# piezo-preamp-tickler_V1-01a_two_buffers.net
KiCad netlist of a schematic drawn in EAGLE
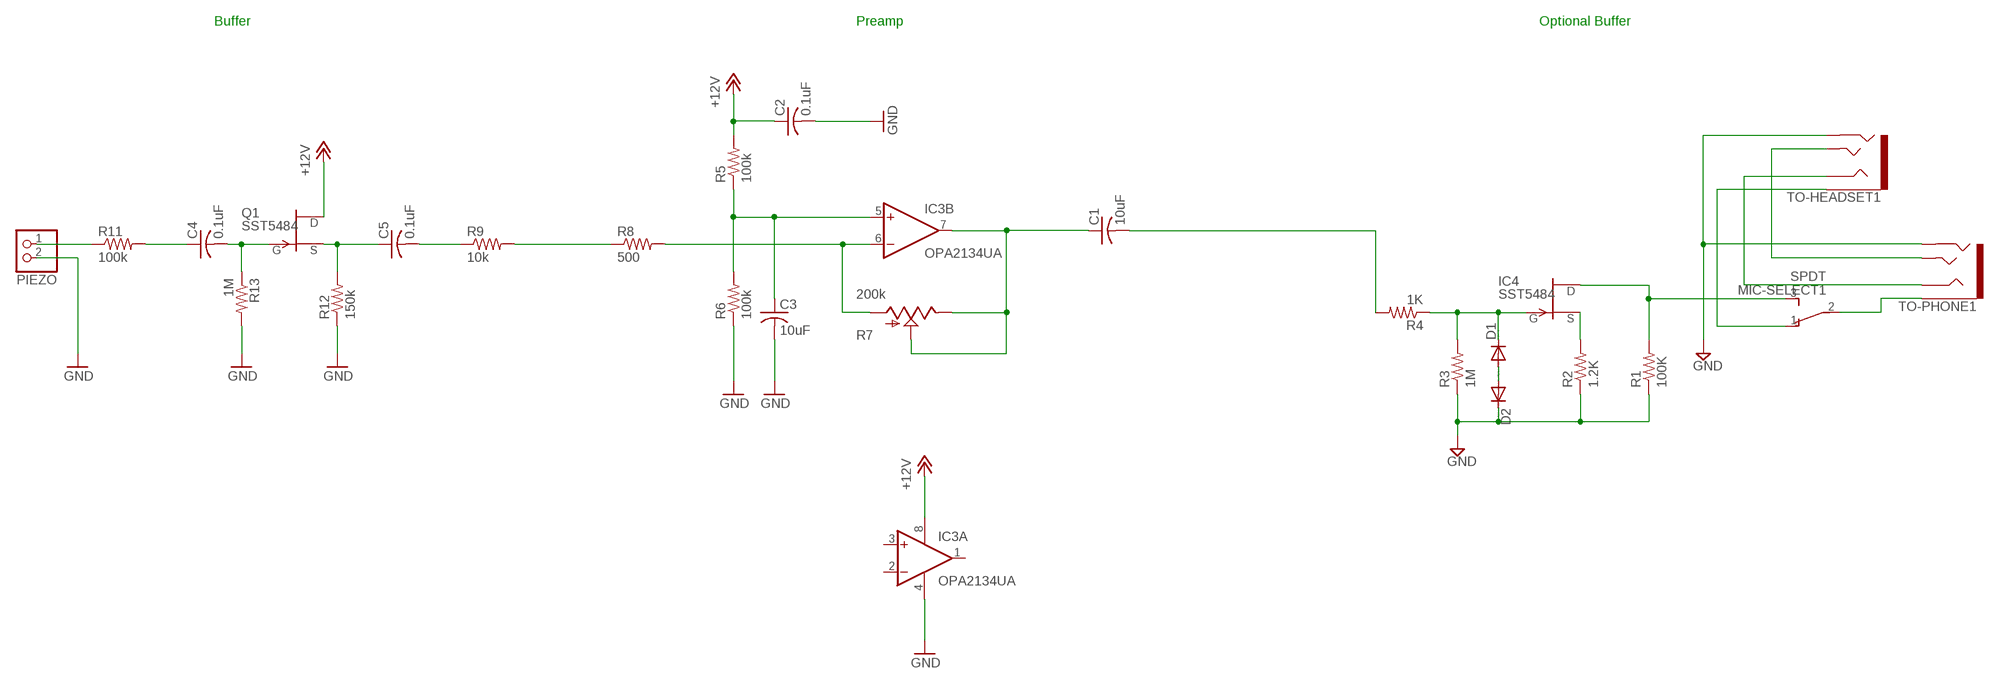
[diagram p0: schematic, sheet 1]
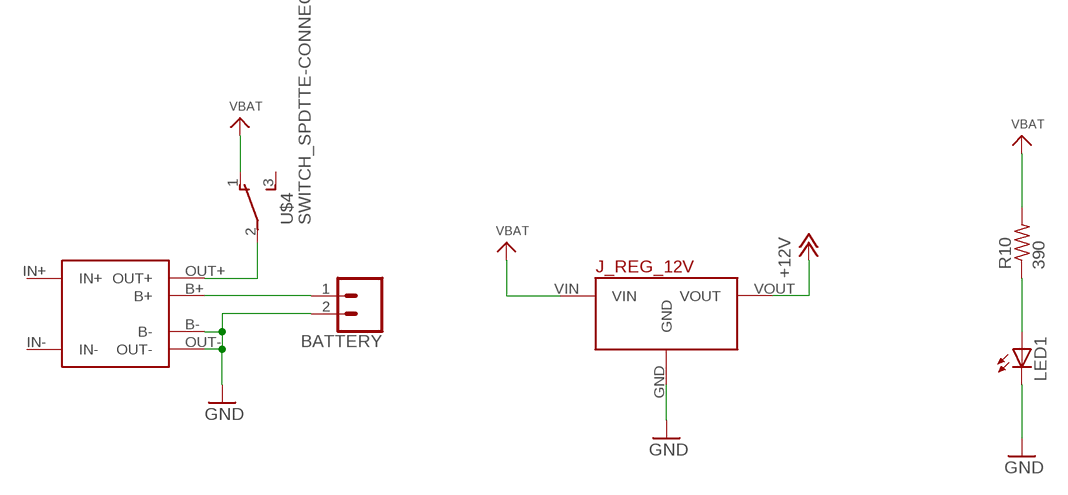
[diagram p1: schematic, sheet 2]

(export (version "E")
  (design (tool "Eeschema 10.0.6"))
  (components
    (comp (ref "BATTERY")
      (value "CONN_02LOCK")
      (footprint "eagle-import:1X02_LOCK")
      (libsource (lib "eagle-import") (part "CONN_02LOCK"))
    )
    (comp (ref "J_REG_12V")
      (value "POLOLU_VOLTAGE_REGULATORS_3PIN")
      (footprint "eagle-import:POLOLU_5V-12V_STEPUP_U3V12F5-U3V12F12")
      (libsource (lib "eagle-import") (part "POLOLU_VOLTAGE_REGULATORS_3PIN"))
    )
    (comp (ref "LED1")
      (value "LED3MM")
      (footprint "eagle-import:LED3MM")
      (libsource (lib "eagle-import") (part "LED3MM"))
    )
    (comp (ref "R10")
      (value "390")
      (footprint "eagle-import:R0805")
      (libsource (lib "eagle-import") (part "adafruit_R-US_R0805"))
    )
    (comp (ref "U$4")
      (value "SWITCH_SPDTTE-CONNECT")
      (footprint "eagle-import:SWITCH_SPDT-TE-CONNECT")
      (libsource (lib "eagle-import") (part "SWITCH_SPDTTE-CONNECT"))
    )
    (comp (ref "U$6")
      (value "TP4056-MODULE")
      (footprint "eagle-import:TP4056-LITHIUM-PROTECTED-MODULE")
      (libsource (lib "eagle-import") (part "TP4056-MODULE"))
    )
    (comp (ref "C1")
      (value "10uF")
      (footprint "eagle-import:C0805")
      (libsource (lib "eagle-import") (part "C-USC0805"))
    )
    (comp (ref "C2")
      (value "0.1uF")
      (footprint "eagle-import:C0805")
      (libsource (lib "eagle-import") (part "C-USC0805"))
    )
    (comp (ref "C3")
      (value "10uF")
      (footprint "eagle-import:C0805")
      (libsource (lib "eagle-import") (part "C-USC0805"))
    )
    (comp (ref "C4")
      (value "0.1uF")
      (footprint "eagle-import:C0805")
      (libsource (lib "eagle-import") (part "C-USC0805"))
    )
    (comp (ref "C5")
      (value "0.1uF")
      (footprint "eagle-import:C0805")
      (libsource (lib "eagle-import") (part "C-USC0805"))
    )
    (comp (ref "D1")
      (value "DIODE-SOD123")
      (footprint "eagle-import:SOD123")
      (libsource (lib "eagle-import") (part "DIODE-SOD123"))
    )
    (comp (ref "D2")
      (value "DIODE-SOD123")
      (footprint "eagle-import:SOD123")
      (libsource (lib "eagle-import") (part "DIODE-SOD123"))
    )
    (comp (ref "IC3")
      (value "OPA2134UA")
      (footprint "eagle-import:SO08")
      (libsource (lib "eagle-import") (part "OPA2UA134"))
    )
    (comp (ref "IC4")
      (value "SST5484")
      (footprint "eagle-import:SOT23")
      (libsource (lib "eagle-import") (part "?548SST4"))
    )
    (comp (ref "MIC-SELECT1")
      (value "SPDT")
      (footprint "eagle-import:SWITCH_SPDT-TE-CONNECT")
      (libsource (lib "eagle-import") (part "SWITCH_SPDTTE-CONNECT"))
    )
    (comp (ref "PIEZO")
      (value "JST_2PIN-THM")
      (footprint "eagle-import:JST-PH-2-THM")
      (libsource (lib "eagle-import") (part "JST_2PIN-THM"))
    )
    (comp (ref "Q1")
      (value "SST5484")
      (footprint "eagle-import:SOT23")
      (libsource (lib "eagle-import") (part "?548SST4"))
    )
    (comp (ref "R1")
      (value "100K")
      (footprint "eagle-import:R0603")
      (libsource (lib "eagle-import") (part "R-US_R0603"))
    )
    (comp (ref "R2")
      (value "1.2K")
      (footprint "eagle-import:R0603")
      (libsource (lib "eagle-import") (part "R-US_R0603"))
    )
    (comp (ref "R3")
      (value "1M")
      (footprint "eagle-import:R0603")
      (libsource (lib "eagle-import") (part "R-US_R0603"))
    )
    (comp (ref "R4")
      (value "1K")
      (footprint "eagle-import:R0603")
      (libsource (lib "eagle-import") (part "R-US_R0603"))
    )
    (comp (ref "R5")
      (value "100k")
      (footprint "eagle-import:R0603")
      (libsource (lib "eagle-import") (part "resistor_R-US_R0603"))
    )
    (comp (ref "R6")
      (value "100k")
      (footprint "eagle-import:R0603")
      (libsource (lib "eagle-import") (part "resistor_R-US_R0603"))
    )
    (comp (ref "R7")
      (value "200k")
      (footprint "eagle-import:TRIMPOT-BOURNS-3306W")
      (libsource (lib "eagle-import") (part "TRIMPOT-BOURNS3306W"))
    )
    (comp (ref "R8")
      (value "500")
      (footprint "eagle-import:R0603")
      (libsource (lib "eagle-import") (part "resistor_R-US_R0603"))
    )
    (comp (ref "R9")
      (value "10k")
      (footprint "eagle-import:R0603")
      (libsource (lib "eagle-import") (part "resistor_R-US_R0603"))
    )
    (comp (ref "R11")
      (value "100k")
      (footprint "eagle-import:R0603")
      (libsource (lib "eagle-import") (part "resistor_R-US_R0603"))
    )
    (comp (ref "R12")
      (value "150k")
      (footprint "eagle-import:R0603")
      (libsource (lib "eagle-import") (part "resistor_R-US_R0603"))
    )
    (comp (ref "R13")
      (value "1M")
      (footprint "eagle-import:R0603")
      (libsource (lib "eagle-import") (part "resistor_R-US_R0603"))
    )
    (comp (ref "TO-HEADSET1")
      (value "AUDIO-JACK3LGPADS")
      (footprint "eagle-import:AUDIO-JACK-TRRS-SMD")
      (libsource (lib "eagle-import") (part "AUDIO-JACK3LGPADS"))
    )
    (comp (ref "TO-PHONE1")
      (value "AUDIO-JACK3LGPADS")
      (footprint "eagle-import:AUDIO-JACK-TRRS-SMD")
      (libsource (lib "eagle-import") (part "AUDIO-JACK3LGPADS"))
    )
  )
  (nets
    (net (code "1") (name "+12V") (class "Default")
      (node (ref "C2") (pin "1") (pinfunction "1_1") (pintype "passive"))
      (node (ref "IC3") (pin "8") (pinfunction "V+_8") (pintype "power_in"))
      (node (ref "J_REG_12V") (pin "VOUT") (pinfunction "VOUT_VOUT") (pintype "bidirectional"))
      (node (ref "Q1") (pin "1") (pinfunction "D_1") (pintype "passive"))
      (node (ref "R5") (pin "2") (pinfunction "2_2") (pintype "passive"))
    )
    (net (code "2") (name "GND") (class "Default")
      (node (ref "BATTERY") (pin "2") (pinfunction "2_2") (pintype "passive"))
      (node (ref "C2") (pin "2") (pinfunction "2_2") (pintype "passive"))
      (node (ref "C3") (pin "2") (pinfunction "2_2") (pintype "passive"))
      (node (ref "D2") (pin "C") (pinfunction "C_C") (pintype "passive"))
      (node (ref "IC3") (pin "4") (pinfunction "V-_4") (pintype "power_in"))
      (node (ref "J_REG_12V") (pin "GND") (pinfunction "GND_GND") (pintype "bidirectional"))
      (node (ref "LED1") (pin "K") (pinfunction "C_K") (pintype "passive"))
      (node (ref "PIEZO") (pin "2") (pinfunction "1_2") (pintype "passive"))
      (node (ref "R1") (pin "1") (pinfunction "1_1") (pintype "passive"))
      (node (ref "R12") (pin "1") (pinfunction "1_1") (pintype "passive"))
      (node (ref "R13") (pin "2") (pinfunction "2_2") (pintype "passive"))
      (node (ref "R2") (pin "1") (pinfunction "1_1") (pintype "passive"))
      (node (ref "R3") (pin "1") (pinfunction "1_1") (pintype "passive"))
      (node (ref "R6") (pin "1") (pinfunction "1_1") (pintype "passive"))
      (node (ref "TO-HEADSET1") (pin "RING2") (pinfunction "RING2_RING2") (pintype "bidirectional"))
      (node (ref "TO-PHONE1") (pin "RING2") (pinfunction "RING2_RING2") (pintype "bidirectional"))
      (node (ref "U$6") (pin "B-") (pinfunction "B-_B-") (pintype "power_in"))
      (node (ref "U$6") (pin "OUT-") (pinfunction "OUT-_OUT-") (pintype "power_in"))
    )
    (net (code "3") (name "IN+") (class "Default")
      (node (ref "U$6") (pin "IN+") (pinfunction "IN+_IN+") (pintype "power_in"))
    )
    (net (code "4") (name "IN-") (class "Default")
      (node (ref "U$6") (pin "IN-") (pinfunction "IN-_IN-") (pintype "power_in"))
    )
    (net (code "5") (name "Net-(BATTERY-Pad1)") (class "Default")
      (node (ref "BATTERY") (pin "1") (pinfunction "1_1") (pintype "passive"))
      (node (ref "U$6") (pin "B+") (pinfunction "B+_B+") (pintype "power_in"))
    )
    (net (code "6") (name "Net-(C1-Pad2)") (class "Default")
      (node (ref "C1") (pin "2") (pinfunction "2_2") (pintype "passive"))
      (node (ref "R4") (pin "2") (pinfunction "2_2") (pintype "passive"))
    )
    (net (code "7") (name "Net-(C4-Pad1)") (class "Default")
      (node (ref "C4") (pin "1") (pinfunction "1_1") (pintype "passive"))
      (node (ref "R11") (pin "2") (pinfunction "2_2") (pintype "passive"))
    )
    (net (code "8") (name "Net-(C5-Pad2)") (class "Default")
      (node (ref "C5") (pin "2") (pinfunction "2_2") (pintype "passive"))
      (node (ref "R9") (pin "1") (pinfunction "1_1") (pintype "passive"))
    )
    (net (code "9") (name "Net-(D1-PadA)") (class "Default")
      (node (ref "D1") (pin "A") (pinfunction "A_A") (pintype "passive"))
      (node (ref "D2") (pin "A") (pinfunction "A_A") (pintype "passive"))
    )
    (net (code "10") (name "Net-(IC3B-+IN)") (class "Default")
      (node (ref "C3") (pin "1") (pinfunction "1_1") (pintype "passive"))
      (node (ref "IC3") (pin "5") (pinfunction "+IN_5") (pintype "input"))
      (node (ref "R5") (pin "1") (pinfunction "1_1") (pintype "passive"))
      (node (ref "R6") (pin "2") (pinfunction "2_2") (pintype "passive"))
    )
    (net (code "11") (name "Net-(IC3B--IN)") (class "Default")
      (node (ref "IC3") (pin "6") (pinfunction "-IN_6") (pintype "input"))
      (node (ref "R7") (pin "P$1") (pinfunction "IN_P$1") (pintype "passive"))
      (node (ref "R8") (pin "2") (pinfunction "2_2") (pintype "passive"))
    )
    (net (code "12") (name "Net-(IC3B-OUT)") (class "Default")
      (node (ref "C1") (pin "1") (pinfunction "1_1") (pintype "passive"))
      (node (ref "IC3") (pin "7") (pinfunction "OUT_7") (pintype "output"))
      (node (ref "R7") (pin "P$2") (pinfunction "WIPER_P$2") (pintype "passive"))
      (node (ref "R7") (pin "P$3") (pinfunction "OUT_P$3") (pintype "passive"))
    )
    (net (code "13") (name "Net-(IC4-D)") (class "Default")
      (node (ref "IC4") (pin "1") (pinfunction "D_1") (pintype "passive"))
      (node (ref "MIC-SELECT1") (pin "3") (pinfunction "3_3") (pintype "passive"))
      (node (ref "R1") (pin "2") (pinfunction "2_2") (pintype "passive"))
    )
    (net (code "14") (name "Net-(IC4-G)") (class "Default")
      (node (ref "D1") (pin "C") (pinfunction "C_C") (pintype "passive"))
      (node (ref "IC4") (pin "3") (pinfunction "G_3") (pintype "passive"))
      (node (ref "R3") (pin "2") (pinfunction "2_2") (pintype "passive"))
      (node (ref "R4") (pin "1") (pinfunction "1_1") (pintype "passive"))
    )
    (net (code "15") (name "Net-(IC4-S)") (class "Default")
      (node (ref "IC4") (pin "2") (pinfunction "S_2") (pintype "passive"))
      (node (ref "R2") (pin "2") (pinfunction "2_2") (pintype "passive"))
    )
    (net (code "16") (name "Net-(LED1-PadA)") (class "Default")
      (node (ref "LED1") (pin "A") (pinfunction "A_A") (pintype "passive"))
      (node (ref "R10") (pin "1") (pinfunction "1_1") (pintype "passive"))
    )
    (net (code "17") (name "Net-(MIC-SELECT1-Pad1)") (class "Default")
      (node (ref "MIC-SELECT1") (pin "1") (pinfunction "1_1") (pintype "passive"))
      (node (ref "TO-HEADSET1") (pin "EARTH") (pinfunction "EARTH_EARTH") (pintype "bidirectional"))
    )
    (net (code "18") (name "Net-(MIC-SELECT1-Pad2)") (class "Default")
      (node (ref "MIC-SELECT1") (pin "2") (pinfunction "2_2") (pintype "passive"))
      (node (ref "TO-PHONE1") (pin "EARTH") (pinfunction "EARTH_EARTH") (pintype "bidirectional"))
    )
    (net (code "19") (name "Net-(PIEZO-2)") (class "Default")
      (node (ref "PIEZO") (pin "1") (pinfunction "2_1") (pintype "passive"))
      (node (ref "R11") (pin "1") (pinfunction "1_1") (pintype "passive"))
    )
    (net (code "20") (name "Net-(Q1-G)") (class "Default")
      (node (ref "C4") (pin "2") (pinfunction "2_2") (pintype "passive"))
      (node (ref "Q1") (pin "3") (pinfunction "G_3") (pintype "passive"))
      (node (ref "R13") (pin "1") (pinfunction "1_1") (pintype "passive"))
    )
    (net (code "21") (name "Net-(Q1-S)") (class "Default")
      (node (ref "C5") (pin "1") (pinfunction "1_1") (pintype "passive"))
      (node (ref "Q1") (pin "2") (pinfunction "S_2") (pintype "passive"))
      (node (ref "R12") (pin "2") (pinfunction "2_2") (pintype "passive"))
    )
    (net (code "22") (name "Net-(R8-Pad1)") (class "Default")
      (node (ref "R8") (pin "1") (pinfunction "1_1") (pintype "passive"))
      (node (ref "R9") (pin "2") (pinfunction "2_2") (pintype "passive"))
    )
    (net (code "23") (name "Net-(TO-HEADSET1-PadRING1)") (class "Default")
      (node (ref "TO-HEADSET1") (pin "RING1") (pinfunction "RING1_RING1") (pintype "bidirectional"))
      (node (ref "TO-PHONE1") (pin "RING1") (pinfunction "RING1_RING1") (pintype "bidirectional"))
    )
    (net (code "24") (name "Net-(TO-HEADSET1-PadTIP)") (class "Default")
      (node (ref "TO-HEADSET1") (pin "TIP") (pinfunction "TIP_TIP") (pintype "bidirectional"))
      (node (ref "TO-PHONE1") (pin "TIP") (pinfunction "TIP_TIP") (pintype "bidirectional"))
    )
    (net (code "25") (name "Net-(U$4-Pad2)") (class "Default")
      (node (ref "U$4") (pin "2") (pinfunction "2_2") (pintype "passive"))
      (node (ref "U$6") (pin "OUT+") (pinfunction "OUT+_OUT+") (pintype "power_in"))
    )
    (net (code "26") (name "VBAT") (class "Default")
      (node (ref "J_REG_12V") (pin "VIN") (pinfunction "VIN_VIN") (pintype "bidirectional"))
      (node (ref "R10") (pin "2") (pinfunction "2_2") (pintype "passive"))
      (node (ref "U$4") (pin "1") (pinfunction "1_1") (pintype "passive"))
    )
    (net (code "27") (name "unconnected-(IC3A-+IN-Pad3)") (class "Default")
      (node (ref "IC3") (pin "3") (pinfunction "+IN_3") (pintype "input"))
    )
    (net (code "28") (name "unconnected-(IC3A--IN-Pad2)") (class "Default")
      (node (ref "IC3") (pin "2") (pinfunction "-IN_2") (pintype "input"))
    )
    (net (code "29") (name "unconnected-(IC3A-OUT-Pad1)") (class "Default")
      (node (ref "IC3") (pin "1") (pinfunction "OUT_1") (pintype "output"))
    )
    (net (code "30") (name "unconnected-(U$4-Pad3)") (class "Default")
      (node (ref "U$4") (pin "3") (pinfunction "3_3") (pintype "passive"))
    )
  )
)
